# RcrSend.net
KiCad netlist of a schematic drawn in EAGLE
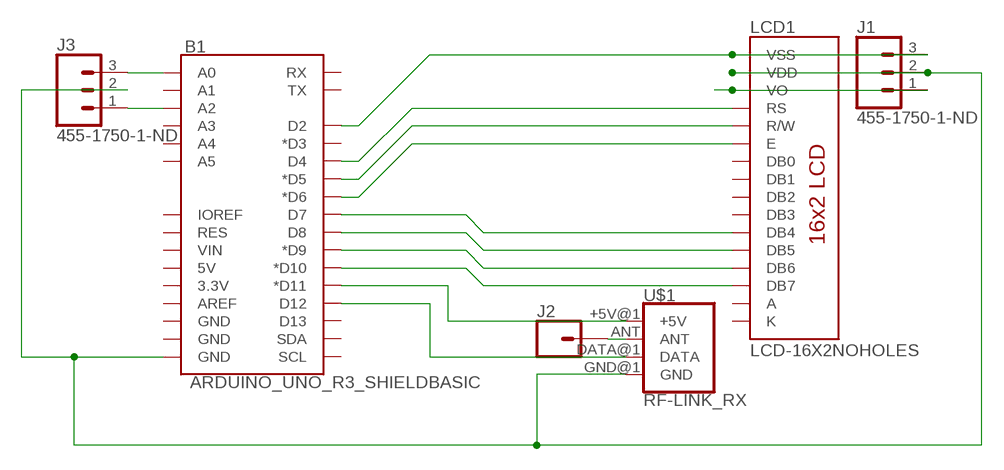
[diagram p0: schematic, sheet 1]

(export (version "E")
  (design (tool "Eeschema 10.0.6"))
  (components
    (comp (ref "B1")
      (value "ARDUINO_UNO_R3_SHIELDBASIC")
      (footprint "eagle-import:UNO_R3_SHIELD")
      (libsource (lib "eagle-import") (part "ARDUINO_UNO_R3_SHIELDBASIC"))
    )
    (comp (ref "J1")
      (value "455-1750-1-ND")
      (footprint "eagle-import:1X03")
      (libsource (lib "eagle-import") (part "CONN_03"))
    )
    (comp (ref "J2")
      (value "CONN_01")
      (footprint "eagle-import:1X01")
      (libsource (lib "eagle-import") (part "CONN_01"))
    )
    (comp (ref "J3")
      (value "455-1750-1-ND")
      (footprint "eagle-import:1X03")
      (libsource (lib "eagle-import") (part "CONN_03"))
    )
    (comp (ref "LCD1")
      (value "LCD-16X2NOHOLES")
      (footprint "eagle-import:LCD-16X2_NOHOLESNOSILK")
      (libsource (lib "eagle-import") (part "LCD-16X2NOHOLES"))
    )
    (comp (ref "U$1")
      (value "RF-LINK_RX")
      (footprint "eagle-import:RF-LINK_RX")
      (libsource (lib "eagle-import") (part "RF-LINK_RX"))
    )
  )
  (nets
    (net (code "1") (name "/A") (class "Default")
      (node (ref "LCD1") (pin "15") (pinfunction "A_15") (pintype "power_in"))
    )
    (net (code "2") (name "/K") (class "Default")
      (node (ref "LCD1") (pin "16") (pinfunction "K_16") (pintype "power_in"))
    )
    (net (code "3") (name "Net-(B1-*D5)") (class "Default")
      (node (ref "B1") (pin "D5") (pinfunction "*D5_D5") (pintype "bidirectional"))
      (node (ref "LCD1") (pin "5") (pinfunction "R/W_5") (pintype "input"))
    )
    (net (code "4") (name "Net-(B1-*D6)") (class "Default")
      (node (ref "B1") (pin "D6") (pinfunction "*D6_D6") (pintype "bidirectional"))
      (node (ref "LCD1") (pin "6") (pinfunction "E_6") (pintype "input"))
    )
    (net (code "5") (name "Net-(B1-*D9)") (class "Default")
      (node (ref "B1") (pin "D9") (pinfunction "*D9_D9") (pintype "bidirectional"))
      (node (ref "LCD1") (pin "13") (pinfunction "DB6_13") (pintype "bidirectional"))
    )
    (net (code "6") (name "Net-(B1-*D10)") (class "Default")
      (node (ref "B1") (pin "D10") (pinfunction "*D10_D10") (pintype "bidirectional"))
      (node (ref "LCD1") (pin "14") (pinfunction "DB7_14") (pintype "bidirectional"))
    )
    (net (code "7") (name "Net-(B1-*D11)") (class "Default")
      (node (ref "B1") (pin "D11") (pinfunction "*D11_D11") (pintype "bidirectional"))
      (node (ref "U$1") (pin "+5V@1") (pinfunction "+5V_+5V@1") (pintype "power_in"))
    )
    (net (code "8") (name "Net-(B1-PadA0)") (class "Default")
      (node (ref "B1") (pin "A0") (pinfunction "A0_A0") (pintype "bidirectional"))
      (node (ref "J3") (pin "3") (pinfunction "3_3") (pintype "passive"))
    )
    (net (code "9") (name "Net-(B1-PadA2)") (class "Default")
      (node (ref "B1") (pin "A2") (pinfunction "A2_A2") (pintype "bidirectional"))
      (node (ref "J3") (pin "1") (pinfunction "1_1") (pintype "passive"))
    )
    (net (code "10") (name "Net-(J2-Pad1)") (class "Default")
      (node (ref "J2") (pin "1") (pinfunction "1_1") (pintype "passive"))
      (node (ref "U$1") (pin "ANT") (pinfunction "ANT_ANT") (pintype "passive"))
    )
    (net (code "11") (name "Net-(LCD1-DB4)") (class "Default")
      (node (ref "B1") (pin "D7") (pinfunction "D7_D7") (pintype "bidirectional"))
      (node (ref "LCD1") (pin "11") (pinfunction "DB4_11") (pintype "bidirectional"))
    )
    (net (code "12") (name "Net-(LCD1-DB5)") (class "Default")
      (node (ref "B1") (pin "D8") (pinfunction "D8_D8") (pintype "bidirectional"))
      (node (ref "LCD1") (pin "12") (pinfunction "DB5_12") (pintype "bidirectional"))
    )
    (net (code "13") (name "Net-(LCD1-RS)") (class "Default")
      (node (ref "B1") (pin "D4") (pinfunction "D4_D4") (pintype "bidirectional"))
      (node (ref "LCD1") (pin "4") (pinfunction "RS_4") (pintype "input"))
    )
    (net (code "14") (name "Net-(LCD1-VDD)") (class "Default")
      (node (ref "B1") (pin "GND@0") (pinfunction "GND_GND@0") (pintype "bidirectional"))
      (node (ref "J1") (pin "2") (pinfunction "2_2") (pintype "passive"))
      (node (ref "J3") (pin "2") (pinfunction "2_2") (pintype "passive"))
      (node (ref "LCD1") (pin "2") (pinfunction "VDD_2") (pintype "power_in"))
      (node (ref "U$1") (pin "GND@1") (pinfunction "GND_GND@1") (pintype "power_in"))
    )
    (net (code "15") (name "Net-(LCD1-VO)") (class "Default")
      (node (ref "J1") (pin "1") (pinfunction "1_1") (pintype "passive"))
      (node (ref "LCD1") (pin "3") (pinfunction "VO_3") (pintype "bidirectional"))
    )
    (net (code "16") (name "Net-(LCD1-VSS)") (class "Default")
      (node (ref "B1") (pin "D2") (pinfunction "D2_D2") (pintype "bidirectional"))
      (node (ref "J1") (pin "3") (pinfunction "3_3") (pintype "passive"))
      (node (ref "LCD1") (pin "1") (pinfunction "VSS_1") (pintype "power_in"))
    )
    (net (code "17") (name "Net-(U$1-DATA)") (class "Default")
      (node (ref "B1") (pin "D12") (pinfunction "D12_D12") (pintype "bidirectional"))
      (node (ref "U$1") (pin "DATA@1") (pinfunction "DATA_DATA@1") (pintype "input"))
    )
    (net (code "18") (name "unconnected-(B1-*D3-PadD3)") (class "Default")
      (node (ref "B1") (pin "D3") (pinfunction "*D3_D3") (pintype "bidirectional"))
    )
    (net (code "19") (name "unconnected-(B1-GND-PadGND@1)") (class "Default")
      (node (ref "B1") (pin "GND@1") (pinfunction "GND_GND@1") (pintype "bidirectional"))
    )
    (net (code "20") (name "unconnected-(B1-GND-PadGND@2)") (class "Default")
      (node (ref "B1") (pin "GND@2") (pinfunction "GND_GND@2") (pintype "bidirectional"))
    )
    (net (code "21") (name "unconnected-(B1-Pad3.3V)") (class "Default")
      (node (ref "B1") (pin "3.3V") (pinfunction "3.3V_3.3V") (pintype "bidirectional"))
    )
    (net (code "22") (name "unconnected-(B1-Pad5V)") (class "Default")
      (node (ref "B1") (pin "5V") (pinfunction "5V_5V") (pintype "bidirectional"))
    )
    (net (code "23") (name "unconnected-(B1-PadA1)") (class "Default")
      (node (ref "B1") (pin "A1") (pinfunction "A1_A1") (pintype "bidirectional"))
    )
    (net (code "24") (name "unconnected-(B1-PadA3)") (class "Default")
      (node (ref "B1") (pin "A3") (pinfunction "A3_A3") (pintype "bidirectional"))
    )
    (net (code "25") (name "unconnected-(B1-PadA4)") (class "Default")
      (node (ref "B1") (pin "A4") (pinfunction "A4_A4") (pintype "bidirectional"))
    )
    (net (code "26") (name "unconnected-(B1-PadA5)") (class "Default")
      (node (ref "B1") (pin "A5") (pinfunction "A5_A5") (pintype "bidirectional"))
    )
    (net (code "27") (name "unconnected-(B1-PadAREF)") (class "Default")
      (node (ref "B1") (pin "AREF") (pinfunction "AREF_AREF") (pintype "bidirectional"))
    )
    (net (code "28") (name "unconnected-(B1-PadD13)") (class "Default")
      (node (ref "B1") (pin "D13") (pinfunction "D13_D13") (pintype "bidirectional"))
    )
    (net (code "29") (name "unconnected-(B1-PadIOREF)") (class "Default")
      (node (ref "B1") (pin "IOREF") (pinfunction "IOREF_IOREF") (pintype "bidirectional"))
    )
    (net (code "30") (name "unconnected-(B1-PadRES)") (class "Default")
      (node (ref "B1") (pin "RES") (pinfunction "RES_RES") (pintype "bidirectional"))
    )
    (net (code "31") (name "unconnected-(B1-PadRX)") (class "Default")
      (node (ref "B1") (pin "RX") (pinfunction "RX_RX") (pintype "bidirectional"))
    )
    (net (code "32") (name "unconnected-(B1-PadSCL)") (class "Default")
      (node (ref "B1") (pin "SCL") (pinfunction "SCL_SCL") (pintype "bidirectional"))
    )
    (net (code "33") (name "unconnected-(B1-PadSDA)") (class "Default")
      (node (ref "B1") (pin "SDA") (pinfunction "SDA_SDA") (pintype "bidirectional"))
    )
    (net (code "34") (name "unconnected-(B1-PadTX)") (class "Default")
      (node (ref "B1") (pin "TX") (pinfunction "TX_TX") (pintype "bidirectional"))
    )
    (net (code "35") (name "unconnected-(B1-PadVIN)") (class "Default")
      (node (ref "B1") (pin "VIN") (pinfunction "VIN_VIN") (pintype "bidirectional"))
    )
    (net (code "36") (name "unconnected-(LCD1-DB0-Pad7)") (class "Default")
      (node (ref "LCD1") (pin "7") (pinfunction "DB0_7") (pintype "bidirectional"))
    )
    (net (code "37") (name "unconnected-(LCD1-DB1-Pad8)") (class "Default")
      (node (ref "LCD1") (pin "8") (pinfunction "DB1_8") (pintype "bidirectional"))
    )
    (net (code "38") (name "unconnected-(LCD1-DB2-Pad9)") (class "Default")
      (node (ref "LCD1") (pin "9") (pinfunction "DB2_9") (pintype "bidirectional"))
    )
    (net (code "39") (name "unconnected-(LCD1-DB3-Pad10)") (class "Default")
      (node (ref "LCD1") (pin "10") (pinfunction "DB3_10") (pintype "bidirectional"))
    )
  )
)
